# ROBOT_SCH.net
KiCad netlist of a schematic drawn in Altium Designer
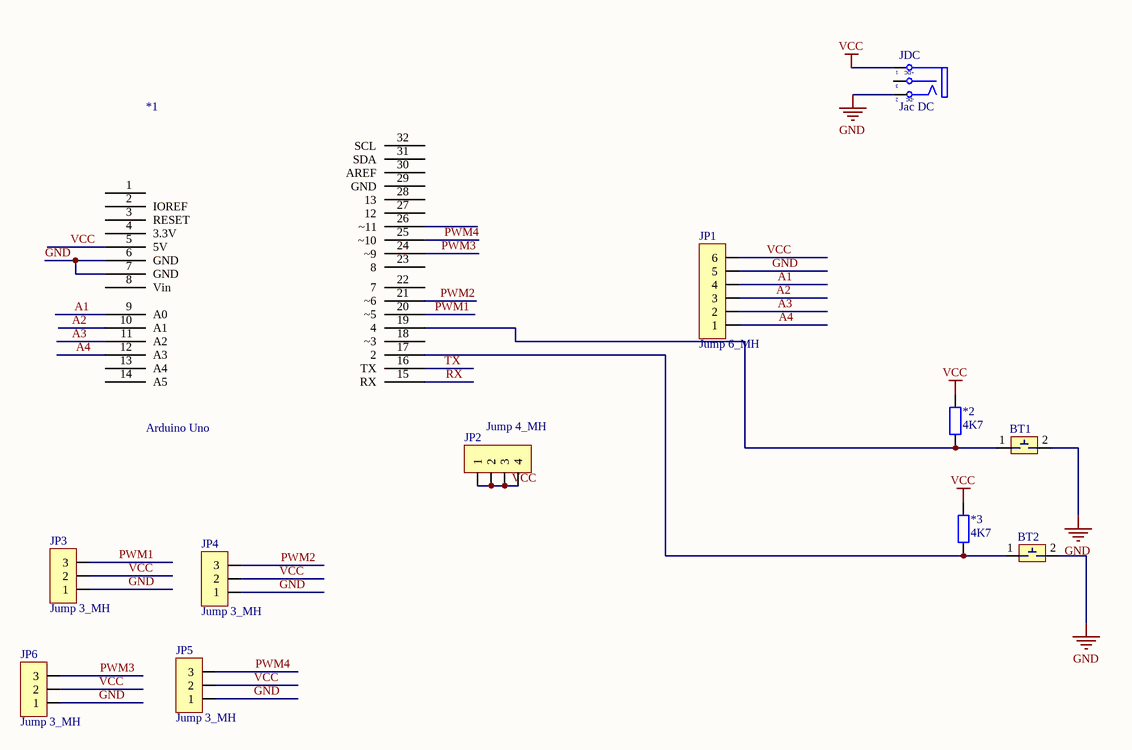
[diagram p0: ROBOT_SCH.SchDoc]

(export (version "E")
  (design (tool "Eeschema 10.0.6"))
  (components
    (comp (ref "*1")
      (value "Arduino Uno")
      (footprint "ARDUINO UNO")
      (libsource (lib "MH_DA_THU_VIEN_ALTIUM_19112016") (part "Arduino Uno"))
    )
    (comp (ref "*2")
      (value "4K7")
      (footprint "Tro SMD 0805")
      (description "TRO_SMD_0805")
      (libsource (lib "MH_DA_THU_VIEN_ALTIUM_19112016") (part "TRO_SMD_0805_MH"))
    )
    (comp (ref "*3")
      (value "4K7")
      (footprint "Tro SMD 0805")
      (description "TRO_SMD_0805")
      (libsource (lib "MH_DA_THU_VIEN_ALTIUM_19112016") (part "TRO_SMD_0805_MH"))
    )
    (comp (ref "BT1")
      (value "BUTTON 4P 6x6_MH")
      (footprint "BUTTON 4 PIN(6*6)")
      (description "Nút nhấn 4 chân, 6x6mm, cắm")
      (libsource (lib "MH_DA_THU_VIEN_ALTIUM_19112016") (part "BUTTON 4P 6x6_MH"))
    )
    (comp (ref "BT2")
      (value "BUTTON 4P 6x6_MH")
      (footprint "BUTTON 4 PIN(6*6)")
      (description "Nút nhấn 4 chân, 6x6mm, cắm")
      (libsource (lib "MH_DA_THU_VIEN_ALTIUM_19112016") (part "BUTTON 4P 6x6_MH"))
    )
    (comp (ref "JDC")
      (value "Jac DC")
      (footprint "DC-IN")
      (description "Jac DC input")
      (libsource (lib "MH_DA_THU_VIEN_ALTIUM_19112016") (part "JAC_DC_MH"))
    )
    (comp (ref "JP1")
      (value "Jump 6_MH")
      (footprint "Jump 6")
      (description "Jump 6P 2.54")
      (libsource (lib "MH_DA_THU_VIEN_ALTIUM_19112016") (part "Jump 6_MH"))
    )
    (comp (ref "JP2")
      (value "Jump 4_MH")
      (footprint "Jump 4")
      (description "Jump 4P 2.54")
      (libsource (lib "MH_DA_THU_VIEN_ALTIUM_19112016") (part "Jump 4_MH"))
    )
    (comp (ref "JP3")
      (value "Jump 3_MH")
      (footprint "Jump 3")
      (description "Jump 3P 2.54")
      (libsource (lib "MH_DA_THU_VIEN_ALTIUM_19112016") (part "Jump 3_MH"))
    )
    (comp (ref "JP4")
      (value "Jump 3_MH")
      (footprint "Jump 3")
      (description "Jump 3P 2.54")
      (libsource (lib "MH_DA_THU_VIEN_ALTIUM_19112016") (part "Jump 3_MH"))
    )
    (comp (ref "JP5")
      (value "Jump 3_MH")
      (footprint "Jump 3")
      (description "Jump 3P 2.54")
      (libsource (lib "MH_DA_THU_VIEN_ALTIUM_19112016") (part "Jump 3_MH"))
    )
    (comp (ref "JP6")
      (value "Jump 3_MH")
      (footprint "Jump 3")
      (description "Jump 3P 2.54")
      (libsource (lib "MH_DA_THU_VIEN_ALTIUM_19112016") (part "Jump 3_MH"))
    )
  )
  (nets
    (net (code "1") (name "/A1") (class "Default")
      (node (ref "*1") (pin "9") (pinfunction "A0_9") (pintype "passive"))
      (node (ref "JP1") (pin "4") (pinfunction "4_4") (pintype "passive"))
    )
    (net (code "2") (name "/A2") (class "Default")
      (node (ref "*1") (pin "10") (pinfunction "A1_10") (pintype "passive"))
      (node (ref "JP1") (pin "3") (pinfunction "3_3") (pintype "passive"))
    )
    (net (code "3") (name "/A3") (class "Default")
      (node (ref "*1") (pin "11") (pinfunction "A2_11") (pintype "passive"))
      (node (ref "JP1") (pin "2") (pinfunction "2_2") (pintype "passive"))
    )
    (net (code "4") (name "/A4") (class "Default")
      (node (ref "*1") (pin "12") (pinfunction "A3_12") (pintype "passive"))
      (node (ref "JP1") (pin "1") (pinfunction "1_1") (pintype "passive"))
    )
    (net (code "5") (name "/PWM1") (class "Default")
      (node (ref "*1") (pin "20") (pinfunction "~5_20") (pintype "passive"))
      (node (ref "JP3") (pin "3") (pinfunction "3_3") (pintype "passive"))
    )
    (net (code "6") (name "/PWM2") (class "Default")
      (node (ref "*1") (pin "21") (pinfunction "~6_21") (pintype "passive"))
      (node (ref "JP4") (pin "3") (pinfunction "3_3") (pintype "passive"))
    )
    (net (code "7") (name "/PWM3") (class "Default")
      (node (ref "*1") (pin "24") (pinfunction "~9_24") (pintype "passive"))
      (node (ref "JP6") (pin "3") (pinfunction "3_3") (pintype "passive"))
    )
    (net (code "8") (name "/PWM4") (class "Default")
      (node (ref "*1") (pin "25") (pinfunction "~10_25") (pintype "passive"))
      (node (ref "JP5") (pin "3") (pinfunction "3_3") (pintype "passive"))
    )
    (net (code "9") (name "/RX") (class "Default")
      (node (ref "*1") (pin "15") (pinfunction "RX_15") (pintype "passive"))
    )
    (net (code "10") (name "/TX") (class "Default")
      (node (ref "*1") (pin "16") (pinfunction "TX_16") (pintype "passive"))
    )
    (net (code "11") (name "GND") (class "Default")
      (node (ref "*1") (pin "6") (pinfunction "GND_6") (pintype "passive"))
      (node (ref "*1") (pin "7") (pinfunction "GND_7") (pintype "passive"))
      (node (ref "BT1") (pin "2") (pinfunction "2_2") (pintype "passive"))
      (node (ref "BT2") (pin "2") (pinfunction "2_2") (pintype "passive"))
      (node (ref "JDC") (pin "2") (pinfunction "TN_2") (pintype "passive"))
      (node (ref "JP1") (pin "5") (pinfunction "5_5") (pintype "passive"))
      (node (ref "JP3") (pin "1") (pinfunction "1_1") (pintype "passive"))
      (node (ref "JP4") (pin "1") (pinfunction "1_1") (pintype "passive"))
      (node (ref "JP5") (pin "1") (pinfunction "1_1") (pintype "passive"))
      (node (ref "JP6") (pin "1") (pinfunction "1_1") (pintype "passive"))
    )
    (net (code "12") (name "Net-(*1-2)") (class "Default")
      (node (ref "*1") (pin "17") (pinfunction "2_17") (pintype "passive"))
      (node (ref "*3") (pin "1") (pinfunction "1_1") (pintype "passive"))
      (node (ref "BT2") (pin "1") (pinfunction "1_1") (pintype "passive"))
    )
    (net (code "13") (name "Net-(*1-4)") (class "Default")
      (node (ref "*1") (pin "19") (pinfunction "4_19") (pintype "passive"))
      (node (ref "*2") (pin "1") (pinfunction "1_1") (pintype "passive"))
      (node (ref "BT1") (pin "1") (pinfunction "1_1") (pintype "passive"))
    )
    (net (code "14") (name "VCC") (class "Default")
      (node (ref "*1") (pin "5") (pinfunction "5V_5") (pintype "passive"))
      (node (ref "*2") (pin "2") (pinfunction "2_2") (pintype "passive"))
      (node (ref "*3") (pin "2") (pinfunction "2_2") (pintype "passive"))
      (node (ref "JDC") (pin "1") (pinfunction "T_1") (pintype "passive"))
      (node (ref "JP1") (pin "6") (pinfunction "6_6") (pintype "passive"))
      (node (ref "JP2") (pin "1") (pinfunction "1_1") (pintype "passive"))
      (node (ref "JP2") (pin "2") (pinfunction "2_2") (pintype "passive"))
      (node (ref "JP2") (pin "3") (pinfunction "3_3") (pintype "passive"))
      (node (ref "JP2") (pin "4") (pinfunction "4_4") (pintype "passive"))
      (node (ref "JP3") (pin "2") (pinfunction "2_2") (pintype "passive"))
      (node (ref "JP4") (pin "2") (pinfunction "2_2") (pintype "passive"))
      (node (ref "JP5") (pin "2") (pinfunction "2_2") (pintype "passive"))
      (node (ref "JP6") (pin "2") (pinfunction "2_2") (pintype "passive"))
    )
    (net (code "15") (name "unconnected-(*1-3.3V-Pad4)") (class "Default")
      (node (ref "*1") (pin "4") (pinfunction "3.3V_4") (pintype "passive"))
    )
    (net (code "16") (name "unconnected-(*1-7-Pad22)") (class "Default")
      (node (ref "*1") (pin "22") (pinfunction "7_22") (pintype "passive"))
    )
    (net (code "17") (name "unconnected-(*1-8-Pad23)") (class "Default")
      (node (ref "*1") (pin "23") (pinfunction "8_23") (pintype "passive"))
    )
    (net (code "18") (name "unconnected-(*1-12-Pad27)") (class "Default")
      (node (ref "*1") (pin "27") (pinfunction "12_27") (pintype "passive"))
    )
    (net (code "19") (name "unconnected-(*1-13-Pad28)") (class "Default")
      (node (ref "*1") (pin "28") (pinfunction "13_28") (pintype "passive"))
    )
    (net (code "20") (name "unconnected-(*1-A4-Pad13)") (class "Default")
      (node (ref "*1") (pin "13") (pinfunction "A4_13") (pintype "passive"))
    )
    (net (code "21") (name "unconnected-(*1-A5-Pad14)") (class "Default")
      (node (ref "*1") (pin "14") (pinfunction "A5_14") (pintype "passive"))
    )
    (net (code "22") (name "unconnected-(*1-AREF-Pad30)") (class "Default")
      (node (ref "*1") (pin "30") (pinfunction "AREF_30") (pintype "passive"))
    )
    (net (code "23") (name "unconnected-(*1-GND-Pad29)") (class "Default")
      (node (ref "*1") (pin "29") (pinfunction "GND_29") (pintype "passive"))
    )
    (net (code "24") (name "unconnected-(*1-IOREF-Pad2)") (class "Default")
      (node (ref "*1") (pin "2") (pinfunction "IOREF_2") (pintype "passive"))
    )
    (net (code "25") (name "unconnected-(*1-Pad1)") (class "Default")
      (node (ref "*1") (pin "1") (pintype "passive"))
    )
    (net (code "26") (name "unconnected-(*1-RESET-Pad3)") (class "Default")
      (node (ref "*1") (pin "3") (pinfunction "RESET_3") (pintype "passive"))
    )
    (net (code "27") (name "unconnected-(*1-SCL-Pad32)") (class "Default")
      (node (ref "*1") (pin "32") (pinfunction "SCL_32") (pintype "passive"))
    )
    (net (code "28") (name "unconnected-(*1-SDA-Pad31)") (class "Default")
      (node (ref "*1") (pin "31") (pinfunction "SDA_31") (pintype "passive"))
    )
    (net (code "29") (name "unconnected-(*1-Vin-Pad8)") (class "Default")
      (node (ref "*1") (pin "8") (pinfunction "Vin_8") (pintype "passive"))
    )
    (net (code "30") (name "unconnected-(*1-~3-Pad18)") (class "Default")
      (node (ref "*1") (pin "18") (pinfunction "~3_18") (pintype "passive"))
    )
    (net (code "31") (name "unconnected-(*1-~11-Pad26)") (class "Default")
      (node (ref "*1") (pin "26") (pinfunction "~11_26") (pintype "passive"))
    )
    (net (code "32") (name "unconnected-(JDC-S-Pad3)") (class "Default")
      (node (ref "JDC") (pin "3") (pinfunction "S_3") (pintype "power_in"))
    )
  )
)
